# serializer.net
KiCad netlist of a schematic drawn in EAGLE
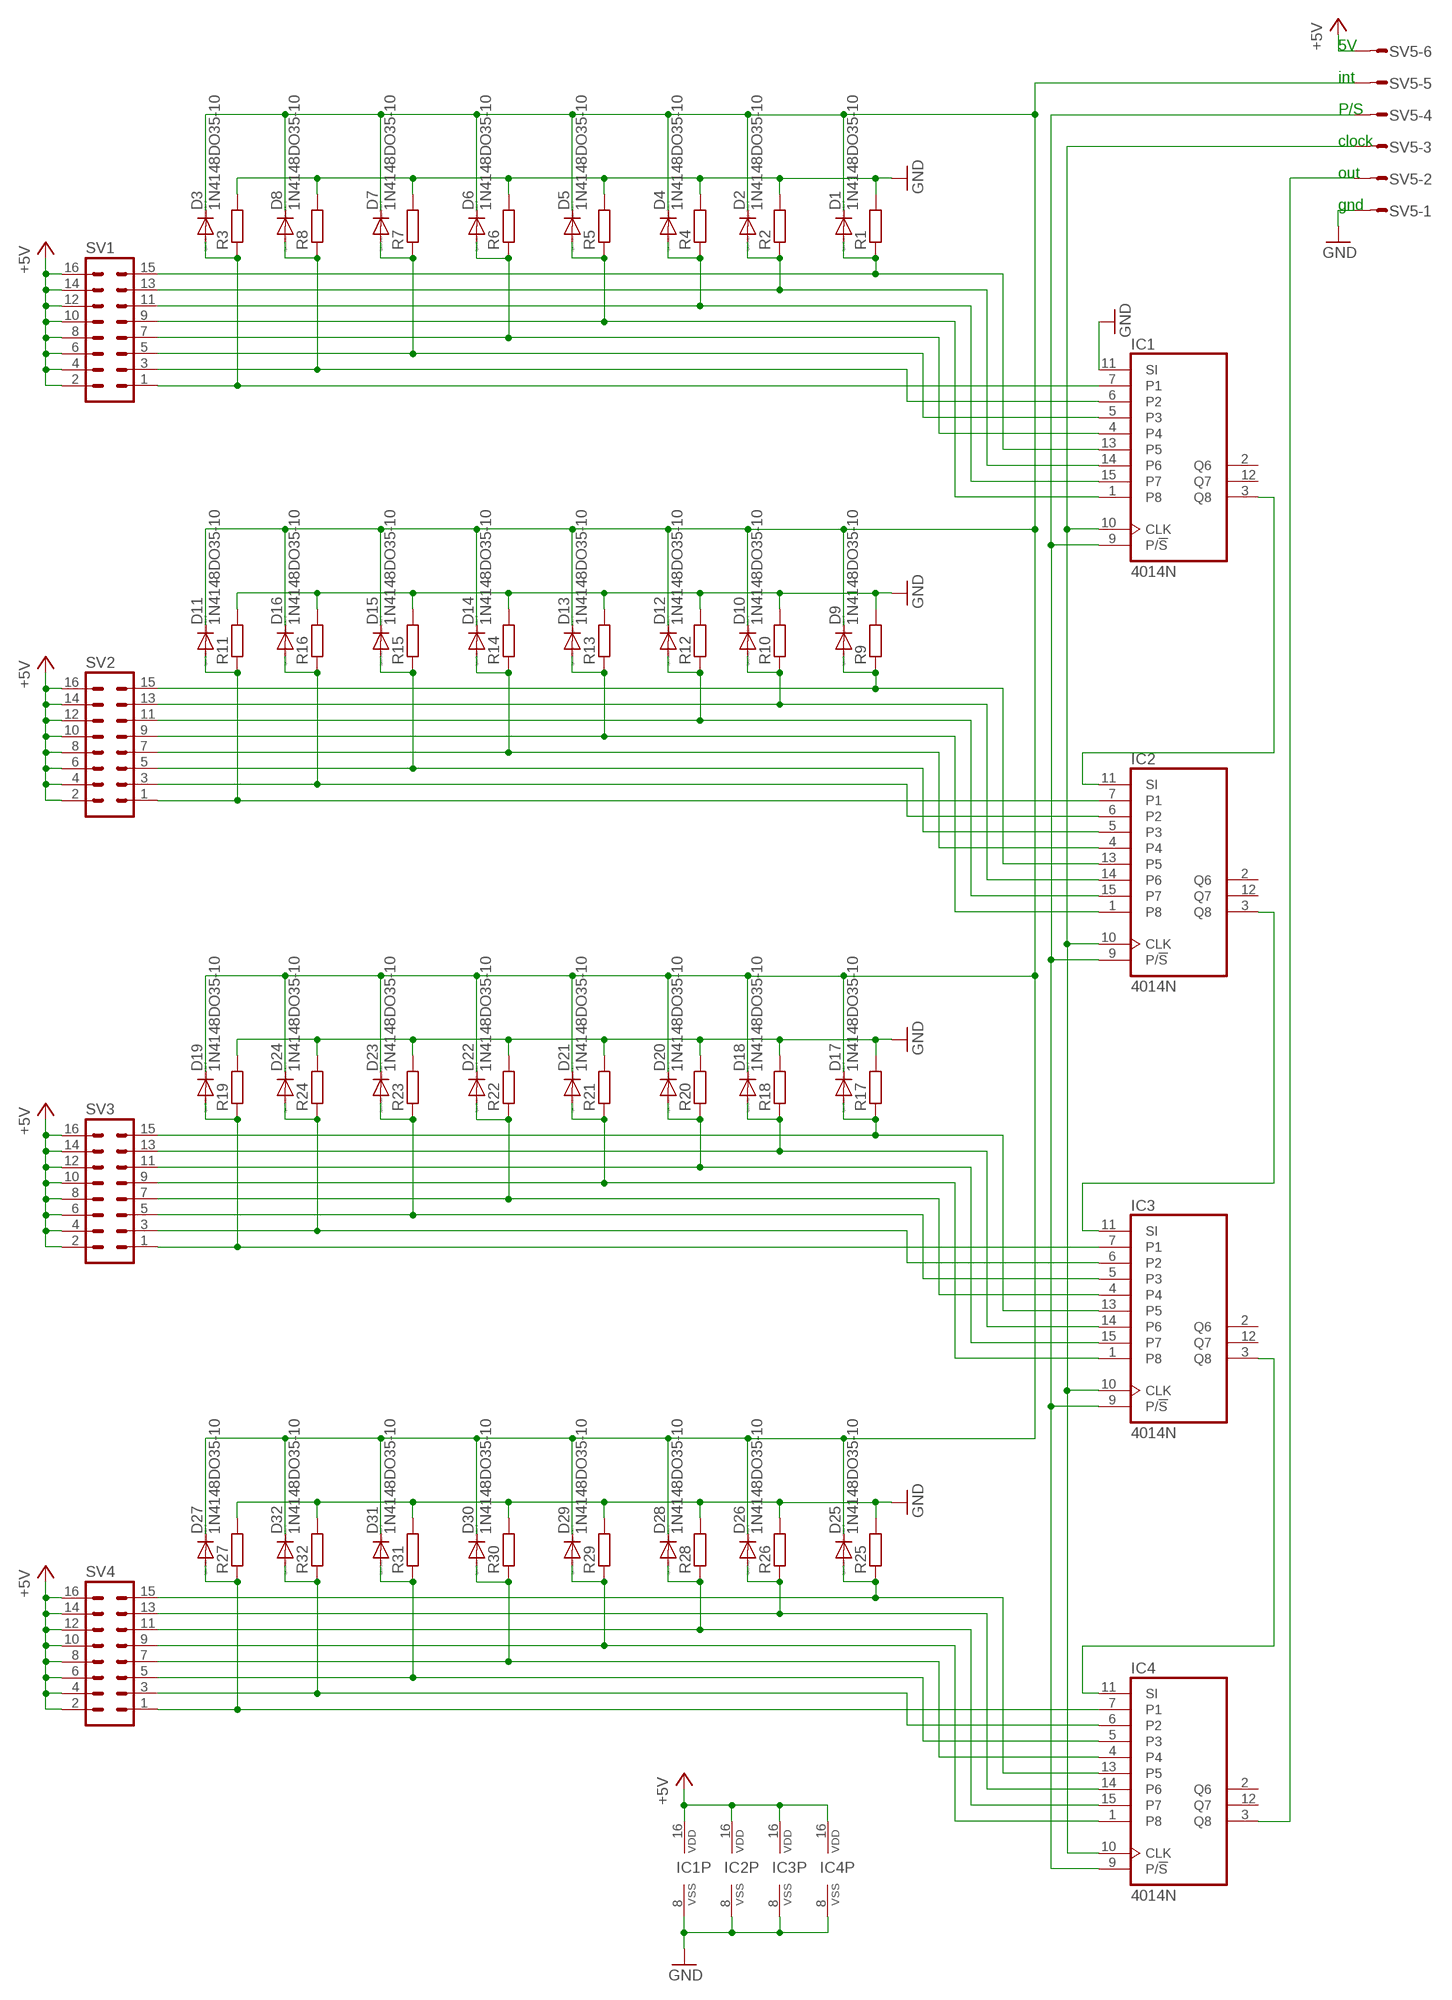
[diagram p0: schematic, sheet 1]

(export (version "E")
  (design (tool "Eeschema 10.0.6"))
  (components
    (comp (ref "D1")
      (value "1N4148DO35-10")
      (footprint "eagle-import:DO35-10")
      (libsource (lib "eagle-import") (part "1N4148DO35-10"))
    )
    (comp (ref "D2")
      (value "1N4148DO35-10")
      (footprint "eagle-import:DO35-10")
      (libsource (lib "eagle-import") (part "1N4148DO35-10"))
    )
    (comp (ref "D3")
      (value "1N4148DO35-10")
      (footprint "eagle-import:DO35-10")
      (libsource (lib "eagle-import") (part "1N4148DO35-10"))
    )
    (comp (ref "D4")
      (value "1N4148DO35-10")
      (footprint "eagle-import:DO35-10")
      (libsource (lib "eagle-import") (part "1N4148DO35-10"))
    )
    (comp (ref "D5")
      (value "1N4148DO35-10")
      (footprint "eagle-import:DO35-10")
      (libsource (lib "eagle-import") (part "1N4148DO35-10"))
    )
    (comp (ref "D6")
      (value "1N4148DO35-10")
      (footprint "eagle-import:DO35-10")
      (libsource (lib "eagle-import") (part "1N4148DO35-10"))
    )
    (comp (ref "D7")
      (value "1N4148DO35-10")
      (footprint "eagle-import:DO35-10")
      (libsource (lib "eagle-import") (part "1N4148DO35-10"))
    )
    (comp (ref "D8")
      (value "1N4148DO35-10")
      (footprint "eagle-import:DO35-10")
      (libsource (lib "eagle-import") (part "1N4148DO35-10"))
    )
    (comp (ref "D9")
      (value "1N4148DO35-10")
      (footprint "eagle-import:DO35-10")
      (libsource (lib "eagle-import") (part "1N4148DO35-10"))
    )
    (comp (ref "D10")
      (value "1N4148DO35-10")
      (footprint "eagle-import:DO35-10")
      (libsource (lib "eagle-import") (part "1N4148DO35-10"))
    )
    (comp (ref "D11")
      (value "1N4148DO35-10")
      (footprint "eagle-import:DO35-10")
      (libsource (lib "eagle-import") (part "1N4148DO35-10"))
    )
    (comp (ref "D12")
      (value "1N4148DO35-10")
      (footprint "eagle-import:DO35-10")
      (libsource (lib "eagle-import") (part "1N4148DO35-10"))
    )
    (comp (ref "D13")
      (value "1N4148DO35-10")
      (footprint "eagle-import:DO35-10")
      (libsource (lib "eagle-import") (part "1N4148DO35-10"))
    )
    (comp (ref "D14")
      (value "1N4148DO35-10")
      (footprint "eagle-import:DO35-10")
      (libsource (lib "eagle-import") (part "1N4148DO35-10"))
    )
    (comp (ref "D15")
      (value "1N4148DO35-10")
      (footprint "eagle-import:DO35-10")
      (libsource (lib "eagle-import") (part "1N4148DO35-10"))
    )
    (comp (ref "D16")
      (value "1N4148DO35-10")
      (footprint "eagle-import:DO35-10")
      (libsource (lib "eagle-import") (part "1N4148DO35-10"))
    )
    (comp (ref "D17")
      (value "1N4148DO35-10")
      (footprint "eagle-import:DO35-10")
      (libsource (lib "eagle-import") (part "1N4148DO35-10"))
    )
    (comp (ref "D18")
      (value "1N4148DO35-10")
      (footprint "eagle-import:DO35-10")
      (libsource (lib "eagle-import") (part "1N4148DO35-10"))
    )
    (comp (ref "D19")
      (value "1N4148DO35-10")
      (footprint "eagle-import:DO35-10")
      (libsource (lib "eagle-import") (part "1N4148DO35-10"))
    )
    (comp (ref "D20")
      (value "1N4148DO35-10")
      (footprint "eagle-import:DO35-10")
      (libsource (lib "eagle-import") (part "1N4148DO35-10"))
    )
    (comp (ref "D21")
      (value "1N4148DO35-10")
      (footprint "eagle-import:DO35-10")
      (libsource (lib "eagle-import") (part "1N4148DO35-10"))
    )
    (comp (ref "D22")
      (value "1N4148DO35-10")
      (footprint "eagle-import:DO35-10")
      (libsource (lib "eagle-import") (part "1N4148DO35-10"))
    )
    (comp (ref "D23")
      (value "1N4148DO35-10")
      (footprint "eagle-import:DO35-10")
      (libsource (lib "eagle-import") (part "1N4148DO35-10"))
    )
    (comp (ref "D24")
      (value "1N4148DO35-10")
      (footprint "eagle-import:DO35-10")
      (libsource (lib "eagle-import") (part "1N4148DO35-10"))
    )
    (comp (ref "D25")
      (value "1N4148DO35-10")
      (footprint "eagle-import:DO35-10")
      (libsource (lib "eagle-import") (part "1N4148DO35-10"))
    )
    (comp (ref "D26")
      (value "1N4148DO35-10")
      (footprint "eagle-import:DO35-10")
      (libsource (lib "eagle-import") (part "1N4148DO35-10"))
    )
    (comp (ref "D27")
      (value "1N4148DO35-10")
      (footprint "eagle-import:DO35-10")
      (libsource (lib "eagle-import") (part "1N4148DO35-10"))
    )
    (comp (ref "D28")
      (value "1N4148DO35-10")
      (footprint "eagle-import:DO35-10")
      (libsource (lib "eagle-import") (part "1N4148DO35-10"))
    )
    (comp (ref "D29")
      (value "1N4148DO35-10")
      (footprint "eagle-import:DO35-10")
      (libsource (lib "eagle-import") (part "1N4148DO35-10"))
    )
    (comp (ref "D30")
      (value "1N4148DO35-10")
      (footprint "eagle-import:DO35-10")
      (libsource (lib "eagle-import") (part "1N4148DO35-10"))
    )
    (comp (ref "D31")
      (value "1N4148DO35-10")
      (footprint "eagle-import:DO35-10")
      (libsource (lib "eagle-import") (part "1N4148DO35-10"))
    )
    (comp (ref "D32")
      (value "1N4148DO35-10")
      (footprint "eagle-import:DO35-10")
      (libsource (lib "eagle-import") (part "1N4148DO35-10"))
    )
    (comp (ref "IC1")
      (value "4014N")
      (footprint "eagle-import:DIL16")
      (libsource (lib "eagle-import") (part "4014N"))
    )
    (comp (ref "IC2")
      (value "4014N")
      (footprint "eagle-import:DIL16")
      (libsource (lib "eagle-import") (part "4014N"))
    )
    (comp (ref "IC3")
      (value "4014N")
      (footprint "eagle-import:DIL16")
      (libsource (lib "eagle-import") (part "4014N"))
    )
    (comp (ref "IC4")
      (value "4014N")
      (footprint "eagle-import:DIL16")
      (libsource (lib "eagle-import") (part "4014N"))
    )
    (comp (ref "R1")
      (value "R-EU_M1206")
      (footprint "eagle-import:M1206")
      (libsource (lib "eagle-import") (part "R-EU_M1206"))
    )
    (comp (ref "R2")
      (value "R-EU_M1206")
      (footprint "eagle-import:M1206")
      (libsource (lib "eagle-import") (part "R-EU_M1206"))
    )
    (comp (ref "R3")
      (value "R-EU_M1206")
      (footprint "eagle-import:M1206")
      (libsource (lib "eagle-import") (part "R-EU_M1206"))
    )
    (comp (ref "R4")
      (value "R-EU_M1206")
      (footprint "eagle-import:M1206")
      (libsource (lib "eagle-import") (part "R-EU_M1206"))
    )
    (comp (ref "R5")
      (value "R-EU_M1206")
      (footprint "eagle-import:M1206")
      (libsource (lib "eagle-import") (part "R-EU_M1206"))
    )
    (comp (ref "R6")
      (value "R-EU_M1206")
      (footprint "eagle-import:M1206")
      (libsource (lib "eagle-import") (part "R-EU_M1206"))
    )
    (comp (ref "R7")
      (value "R-EU_M1206")
      (footprint "eagle-import:M1206")
      (libsource (lib "eagle-import") (part "R-EU_M1206"))
    )
    (comp (ref "R8")
      (value "R-EU_M1206")
      (footprint "eagle-import:M1206")
      (libsource (lib "eagle-import") (part "R-EU_M1206"))
    )
    (comp (ref "R9")
      (value "R-EU_M1206")
      (footprint "eagle-import:M1206")
      (libsource (lib "eagle-import") (part "R-EU_M1206"))
    )
    (comp (ref "R10")
      (value "R-EU_M1206")
      (footprint "eagle-import:M1206")
      (libsource (lib "eagle-import") (part "R-EU_M1206"))
    )
    (comp (ref "R11")
      (value "R-EU_M1206")
      (footprint "eagle-import:M1206")
      (libsource (lib "eagle-import") (part "R-EU_M1206"))
    )
    (comp (ref "R12")
      (value "R-EU_M1206")
      (footprint "eagle-import:M1206")
      (libsource (lib "eagle-import") (part "R-EU_M1206"))
    )
    (comp (ref "R13")
      (value "R-EU_M1206")
      (footprint "eagle-import:M1206")
      (libsource (lib "eagle-import") (part "R-EU_M1206"))
    )
    (comp (ref "R14")
      (value "R-EU_M1206")
      (footprint "eagle-import:M1206")
      (libsource (lib "eagle-import") (part "R-EU_M1206"))
    )
    (comp (ref "R15")
      (value "R-EU_M1206")
      (footprint "eagle-import:M1206")
      (libsource (lib "eagle-import") (part "R-EU_M1206"))
    )
    (comp (ref "R16")
      (value "R-EU_M1206")
      (footprint "eagle-import:M1206")
      (libsource (lib "eagle-import") (part "R-EU_M1206"))
    )
    (comp (ref "R17")
      (value "R-EU_M1206")
      (footprint "eagle-import:M1206")
      (libsource (lib "eagle-import") (part "R-EU_M1206"))
    )
    (comp (ref "R18")
      (value "R-EU_M1206")
      (footprint "eagle-import:M1206")
      (libsource (lib "eagle-import") (part "R-EU_M1206"))
    )
    (comp (ref "R19")
      (value "R-EU_M1206")
      (footprint "eagle-import:M1206")
      (libsource (lib "eagle-import") (part "R-EU_M1206"))
    )
    (comp (ref "R20")
      (value "R-EU_M1206")
      (footprint "eagle-import:M1206")
      (libsource (lib "eagle-import") (part "R-EU_M1206"))
    )
    (comp (ref "R21")
      (value "R-EU_M1206")
      (footprint "eagle-import:M1206")
      (libsource (lib "eagle-import") (part "R-EU_M1206"))
    )
    (comp (ref "R22")
      (value "R-EU_M1206")
      (footprint "eagle-import:M1206")
      (libsource (lib "eagle-import") (part "R-EU_M1206"))
    )
    (comp (ref "R23")
      (value "R-EU_M1206")
      (footprint "eagle-import:M1206")
      (libsource (lib "eagle-import") (part "R-EU_M1206"))
    )
    (comp (ref "R24")
      (value "R-EU_M1206")
      (footprint "eagle-import:M1206")
      (libsource (lib "eagle-import") (part "R-EU_M1206"))
    )
    (comp (ref "R25")
      (value "R-EU_M1206")
      (footprint "eagle-import:M1206")
      (libsource (lib "eagle-import") (part "R-EU_M1206"))
    )
    (comp (ref "R26")
      (value "R-EU_M1206")
      (footprint "eagle-import:M1206")
      (libsource (lib "eagle-import") (part "R-EU_M1206"))
    )
    (comp (ref "R27")
      (value "R-EU_M1206")
      (footprint "eagle-import:M1206")
      (libsource (lib "eagle-import") (part "R-EU_M1206"))
    )
    (comp (ref "R28")
      (value "R-EU_M1206")
      (footprint "eagle-import:M1206")
      (libsource (lib "eagle-import") (part "R-EU_M1206"))
    )
    (comp (ref "R29")
      (value "R-EU_M1206")
      (footprint "eagle-import:M1206")
      (libsource (lib "eagle-import") (part "R-EU_M1206"))
    )
    (comp (ref "R30")
      (value "R-EU_M1206")
      (footprint "eagle-import:M1206")
      (libsource (lib "eagle-import") (part "R-EU_M1206"))
    )
    (comp (ref "R31")
      (value "R-EU_M1206")
      (footprint "eagle-import:M1206")
      (libsource (lib "eagle-import") (part "R-EU_M1206"))
    )
    (comp (ref "R32")
      (value "R-EU_M1206")
      (footprint "eagle-import:M1206")
      (libsource (lib "eagle-import") (part "R-EU_M1206"))
    )
    (comp (ref "SV1")
      (value "MA08-2")
      (footprint "eagle-import:MA08-2")
      (libsource (lib "eagle-import") (part "MA08-2"))
    )
    (comp (ref "SV2")
      (value "MA08-2")
      (footprint "eagle-import:MA08-2")
      (libsource (lib "eagle-import") (part "MA08-2"))
    )
    (comp (ref "SV3")
      (value "MA08-2")
      (footprint "eagle-import:MA08-2")
      (libsource (lib "eagle-import") (part "MA08-2"))
    )
    (comp (ref "SV4")
      (value "MA08-2")
      (footprint "eagle-import:MA08-2")
      (libsource (lib "eagle-import") (part "MA08-2"))
    )
    (comp (ref "SV5")
      (value "S06P")
      (footprint "eagle-import:S06P")
      (libsource (lib "eagle-import") (part "S06P"))
    )
  )
  (nets
    (net (code "1") (name "+5V") (class "Default")
      (node (ref "IC1") (pin "16") (pinfunction "VDD_16") (pintype "power_in"))
      (node (ref "IC2") (pin "16") (pinfunction "VDD_16") (pintype "power_in"))
      (node (ref "IC3") (pin "16") (pinfunction "VDD_16") (pintype "power_in"))
      (node (ref "IC4") (pin "16") (pinfunction "VDD_16") (pintype "power_in"))
      (node (ref "SV1") (pin "10") (pinfunction "10_10") (pintype "passive"))
      (node (ref "SV1") (pin "12") (pinfunction "12_12") (pintype "passive"))
      (node (ref "SV1") (pin "14") (pinfunction "14_14") (pintype "passive"))
      (node (ref "SV1") (pin "16") (pinfunction "16_16") (pintype "passive"))
      (node (ref "SV1") (pin "2") (pinfunction "2_2") (pintype "passive"))
      (node (ref "SV1") (pin "4") (pinfunction "4_4") (pintype "passive"))
      (node (ref "SV1") (pin "6") (pinfunction "6_6") (pintype "passive"))
      (node (ref "SV1") (pin "8") (pinfunction "8_8") (pintype "passive"))
      (node (ref "SV2") (pin "10") (pinfunction "10_10") (pintype "passive"))
      (node (ref "SV2") (pin "12") (pinfunction "12_12") (pintype "passive"))
      (node (ref "SV2") (pin "14") (pinfunction "14_14") (pintype "passive"))
      (node (ref "SV2") (pin "16") (pinfunction "16_16") (pintype "passive"))
      (node (ref "SV2") (pin "2") (pinfunction "2_2") (pintype "passive"))
      (node (ref "SV2") (pin "4") (pinfunction "4_4") (pintype "passive"))
      (node (ref "SV2") (pin "6") (pinfunction "6_6") (pintype "passive"))
      (node (ref "SV2") (pin "8") (pinfunction "8_8") (pintype "passive"))
      (node (ref "SV3") (pin "10") (pinfunction "10_10") (pintype "passive"))
      (node (ref "SV3") (pin "12") (pinfunction "12_12") (pintype "passive"))
      (node (ref "SV3") (pin "14") (pinfunction "14_14") (pintype "passive"))
      (node (ref "SV3") (pin "16") (pinfunction "16_16") (pintype "passive"))
      (node (ref "SV3") (pin "2") (pinfunction "2_2") (pintype "passive"))
      (node (ref "SV3") (pin "4") (pinfunction "4_4") (pintype "passive"))
      (node (ref "SV3") (pin "6") (pinfunction "6_6") (pintype "passive"))
      (node (ref "SV3") (pin "8") (pinfunction "8_8") (pintype "passive"))
      (node (ref "SV4") (pin "10") (pinfunction "10_10") (pintype "passive"))
      (node (ref "SV4") (pin "12") (pinfunction "12_12") (pintype "passive"))
      (node (ref "SV4") (pin "14") (pinfunction "14_14") (pintype "passive"))
      (node (ref "SV4") (pin "16") (pinfunction "16_16") (pintype "passive"))
      (node (ref "SV4") (pin "2") (pinfunction "2_2") (pintype "passive"))
      (node (ref "SV4") (pin "4") (pinfunction "4_4") (pintype "passive"))
      (node (ref "SV4") (pin "6") (pinfunction "6_6") (pintype "passive"))
      (node (ref "SV4") (pin "8") (pinfunction "8_8") (pintype "passive"))
      (node (ref "SV5") (pin "6") (pinfunction "S_6") (pintype "passive"))
    )
    (net (code "2") (name "GND") (class "Default")
      (node (ref "IC1") (pin "11") (pinfunction "SI_11") (pintype "input"))
      (node (ref "IC1") (pin "8") (pinfunction "VSS_8") (pintype "power_in"))
      (node (ref "IC2") (pin "8") (pinfunction "VSS_8") (pintype "power_in"))
      (node (ref "IC3") (pin "8") (pinfunction "VSS_8") (pintype "power_in"))
      (node (ref "IC4") (pin "8") (pinfunction "VSS_8") (pintype "power_in"))
      (node (ref "R1") (pin "2") (pinfunction "2_2") (pintype "passive"))
      (node (ref "R10") (pin "2") (pinfunction "2_2") (pintype "passive"))
      (node (ref "R11") (pin "2") (pinfunction "2_2") (pintype "passive"))
      (node (ref "R12") (pin "2") (pinfunction "2_2") (pintype "passive"))
      (node (ref "R13") (pin "2") (pinfunction "2_2") (pintype "passive"))
      (node (ref "R14") (pin "2") (pinfunction "2_2") (pintype "passive"))
      (node (ref "R15") (pin "2") (pinfunction "2_2") (pintype "passive"))
      (node (ref "R16") (pin "2") (pinfunction "2_2") (pintype "passive"))
      (node (ref "R17") (pin "2") (pinfunction "2_2") (pintype "passive"))
      (node (ref "R18") (pin "2") (pinfunction "2_2") (pintype "passive"))
      (node (ref "R19") (pin "2") (pinfunction "2_2") (pintype "passive"))
      (node (ref "R2") (pin "2") (pinfunction "2_2") (pintype "passive"))
      (node (ref "R20") (pin "2") (pinfunction "2_2") (pintype "passive"))
      (node (ref "R21") (pin "2") (pinfunction "2_2") (pintype "passive"))
      (node (ref "R22") (pin "2") (pinfunction "2_2") (pintype "passive"))
      (node (ref "R23") (pin "2") (pinfunction "2_2") (pintype "passive"))
      (node (ref "R24") (pin "2") (pinfunction "2_2") (pintype "passive"))
      (node (ref "R25") (pin "2") (pinfunction "2_2") (pintype "passive"))
      (node (ref "R26") (pin "2") (pinfunction "2_2") (pintype "passive"))
      (node (ref "R27") (pin "2") (pinfunction "2_2") (pintype "passive"))
      (node (ref "R28") (pin "2") (pinfunction "2_2") (pintype "passive"))
      (node (ref "R29") (pin "2") (pinfunction "2_2") (pintype "passive"))
      (node (ref "R3") (pin "2") (pinfunction "2_2") (pintype "passive"))
      (node (ref "R30") (pin "2") (pinfunction "2_2") (pintype "passive"))
      (node (ref "R31") (pin "2") (pinfunction "2_2") (pintype "passive"))
      (node (ref "R32") (pin "2") (pinfunction "2_2") (pintype "passive"))
      (node (ref "R4") (pin "2") (pinfunction "2_2") (pintype "passive"))
      (node (ref "R5") (pin "2") (pinfunction "2_2") (pintype "passive"))
      (node (ref "R6") (pin "2") (pinfunction "2_2") (pintype "passive"))
      (node (ref "R7") (pin "2") (pinfunction "2_2") (pintype "passive"))
      (node (ref "R8") (pin "2") (pinfunction "2_2") (pintype "passive"))
      (node (ref "R9") (pin "2") (pinfunction "2_2") (pintype "passive"))
      (node (ref "SV5") (pin "1") (pinfunction "S_1") (pintype "passive"))
    )
    (net (code "3") (name "Net-(IC1A-CLK)") (class "Default")
      (node (ref "IC1") (pin "10") (pinfunction "CLK_10") (pintype "input"))
      (node (ref "IC2") (pin "10") (pinfunction "CLK_10") (pintype "input"))
      (node (ref "IC3") (pin "10") (pinfunction "CLK_10") (pintype "input"))
      (node (ref "IC4") (pin "10") (pinfunction "CLK_10") (pintype "input"))
      (node (ref "SV5") (pin "3") (pinfunction "S_3") (pintype "passive"))
    )
    (net (code "4") (name "Net-(IC1A-P1)") (class "Default")
      (node (ref "D3") (pin "A") (pinfunction "A_A") (pintype "passive"))
      (node (ref "IC1") (pin "7") (pinfunction "P1_7") (pintype "input"))
      (node (ref "R3") (pin "1") (pinfunction "1_1") (pintype "passive"))
      (node (ref "SV1") (pin "1") (pinfunction "1_1") (pintype "passive"))
    )
    (net (code "5") (name "Net-(IC1A-P2)") (class "Default")
      (node (ref "D8") (pin "A") (pinfunction "A_A") (pintype "passive"))
      (node (ref "IC1") (pin "6") (pinfunction "P2_6") (pintype "input"))
      (node (ref "R8") (pin "1") (pinfunction "1_1") (pintype "passive"))
      (node (ref "SV1") (pin "3") (pinfunction "3_3") (pintype "passive"))
    )
    (net (code "6") (name "Net-(IC1A-P3)") (class "Default")
      (node (ref "D7") (pin "A") (pinfunction "A_A") (pintype "passive"))
      (node (ref "IC1") (pin "5") (pinfunction "P3_5") (pintype "input"))
      (node (ref "R7") (pin "1") (pinfunction "1_1") (pintype "passive"))
      (node (ref "SV1") (pin "5") (pinfunction "5_5") (pintype "passive"))
    )
    (net (code "7") (name "Net-(IC1A-P4)") (class "Default")
      (node (ref "D6") (pin "A") (pinfunction "A_A") (pintype "passive"))
      (node (ref "IC1") (pin "4") (pinfunction "P4_4") (pintype "input"))
      (node (ref "R6") (pin "1") (pinfunction "1_1") (pintype "passive"))
      (node (ref "SV1") (pin "7") (pinfunction "7_7") (pintype "passive"))
    )
    (net (code "8") (name "Net-(IC1A-P5)") (class "Default")
      (node (ref "D1") (pin "A") (pinfunction "A_A") (pintype "passive"))
      (node (ref "IC1") (pin "13") (pinfunction "P5_13") (pintype "input"))
      (node (ref "R1") (pin "1") (pinfunction "1_1") (pintype "passive"))
      (node (ref "SV1") (pin "15") (pinfunction "15_15") (pintype "passive"))
    )
    (net (code "9") (name "Net-(IC1A-P6)") (class "Default")
      (node (ref "D2") (pin "A") (pinfunction "A_A") (pintype "passive"))
      (node (ref "IC1") (pin "14") (pinfunction "P6_14") (pintype "input"))
      (node (ref "R2") (pin "1") (pinfunction "1_1") (pintype "passive"))
      (node (ref "SV1") (pin "13") (pinfunction "13_13") (pintype "passive"))
    )
    (net (code "10") (name "Net-(IC1A-P7)") (class "Default")
      (node (ref "D4") (pin "A") (pinfunction "A_A") (pintype "passive"))
      (node (ref "IC1") (pin "15") (pinfunction "P7_15") (pintype "input"))
      (node (ref "R4") (pin "1") (pinfunction "1_1") (pintype "passive"))
      (node (ref "SV1") (pin "11") (pinfunction "11_11") (pintype "passive"))
    )
    (net (code "11") (name "Net-(IC1A-P8)") (class "Default")
      (node (ref "D5") (pin "A") (pinfunction "A_A") (pintype "passive"))
      (node (ref "IC1") (pin "1") (pinfunction "P8_1") (pintype "input"))
      (node (ref "R5") (pin "1") (pinfunction "1_1") (pintype "passive"))
      (node (ref "SV1") (pin "9") (pinfunction "9_9") (pintype "passive"))
    )
    (net (code "12") (name "Net-(IC1A-P{slash}~{S})") (class "Default")
      (node (ref "IC1") (pin "9") (pinfunction "P/~{S}_9") (pintype "input"))
      (node (ref "IC2") (pin "9") (pinfunction "P/~{S}_9") (pintype "input"))
      (node (ref "IC3") (pin "9") (pinfunction "P/~{S}_9") (pintype "input"))
      (node (ref "IC4") (pin "9") (pinfunction "P/~{S}_9") (pintype "input"))
      (node (ref "SV5") (pin "4") (pinfunction "S_4") (pintype "passive"))
    )
    (net (code "13") (name "Net-(IC1A-Q8)") (class "Default")
      (node (ref "IC1") (pin "3") (pinfunction "Q8_3") (pintype "output"))
      (node (ref "IC2") (pin "11") (pinfunction "SI_11") (pintype "input"))
    )
    (net (code "14") (name "Net-(IC2A-P1)") (class "Default")
      (node (ref "D11") (pin "A") (pinfunction "A_A") (pintype "passive"))
      (node (ref "IC2") (pin "7") (pinfunction "P1_7") (pintype "input"))
      (node (ref "R11") (pin "1") (pinfunction "1_1") (pintype "passive"))
      (node (ref "SV2") (pin "1") (pinfunction "1_1") (pintype "passive"))
    )
    (net (code "15") (name "Net-(IC2A-P2)") (class "Default")
      (node (ref "D16") (pin "A") (pinfunction "A_A") (pintype "passive"))
      (node (ref "IC2") (pin "6") (pinfunction "P2_6") (pintype "input"))
      (node (ref "R16") (pin "1") (pinfunction "1_1") (pintype "passive"))
      (node (ref "SV2") (pin "3") (pinfunction "3_3") (pintype "passive"))
    )
    (net (code "16") (name "Net-(IC2A-P3)") (class "Default")
      (node (ref "D15") (pin "A") (pinfunction "A_A") (pintype "passive"))
      (node (ref "IC2") (pin "5") (pinfunction "P3_5") (pintype "input"))
      (node (ref "R15") (pin "1") (pinfunction "1_1") (pintype "passive"))
      (node (ref "SV2") (pin "5") (pinfunction "5_5") (pintype "passive"))
    )
    (net (code "17") (name "Net-(IC2A-P4)") (class "Default")
      (node (ref "D14") (pin "A") (pinfunction "A_A") (pintype "passive"))
      (node (ref "IC2") (pin "4") (pinfunction "P4_4") (pintype "input"))
      (node (ref "R14") (pin "1") (pinfunction "1_1") (pintype "passive"))
      (node (ref "SV2") (pin "7") (pinfunction "7_7") (pintype "passive"))
    )
    (net (code "18") (name "Net-(IC2A-P5)") (class "Default")
      (node (ref "D9") (pin "A") (pinfunction "A_A") (pintype "passive"))
      (node (ref "IC2") (pin "13") (pinfunction "P5_13") (pintype "input"))
      (node (ref "R9") (pin "1") (pinfunction "1_1") (pintype "passive"))
      (node (ref "SV2") (pin "15") (pinfunction "15_15") (pintype "passive"))
    )
    (net (code "19") (name "Net-(IC2A-P6)") (class "Default")
      (node (ref "D10") (pin "A") (pinfunction "A_A") (pintype "passive"))
      (node (ref "IC2") (pin "14") (pinfunction "P6_14") (pintype "input"))
      (node (ref "R10") (pin "1") (pinfunction "1_1") (pintype "passive"))
      (node (ref "SV2") (pin "13") (pinfunction "13_13") (pintype "passive"))
    )
    (net (code "20") (name "Net-(IC2A-P7)") (class "Default")
      (node (ref "D12") (pin "A") (pinfunction "A_A") (pintype "passive"))
      (node (ref "IC2") (pin "15") (pinfunction "P7_15") (pintype "input"))
      (node (ref "R12") (pin "1") (pinfunction "1_1") (pintype "passive"))
      (node (ref "SV2") (pin "11") (pinfunction "11_11") (pintype "passive"))
    )
    (net (code "21") (name "Net-(IC2A-P8)") (class "Default")
      (node (ref "D13") (pin "A") (pinfunction "A_A") (pintype "passive"))
      (node (ref "IC2") (pin "1") (pinfunction "P8_1") (pintype "input"))
      (node (ref "R13") (pin "1") (pinfunction "1_1") (pintype "passive"))
      (node (ref "SV2") (pin "9") (pinfunction "9_9") (pintype "passive"))
    )
    (net (code "22") (name "Net-(IC2A-Q8)") (class "Default")
      (node (ref "IC2") (pin "3") (pinfunction "Q8_3") (pintype "output"))
      (node (ref "IC3") (pin "11") (pinfunction "SI_11") (pintype "input"))
    )
    (net (code "23") (name "Net-(IC3A-P1)") (class "Default")
      (node (ref "D19") (pin "A") (pinfunction "A_A") (pintype "passive"))
      (node (ref "IC3") (pin "7") (pinfunction "P1_7") (pintype "input"))
      (node (ref "R19") (pin "1") (pinfunction "1_1") (pintype "passive"))
      (node (ref "SV3") (pin "1") (pinfunction "1_1") (pintype "passive"))
    )
    (net (code "24") (name "Net-(IC3A-P2)") (class "Default")
      (node (ref "D24") (pin "A") (pinfunction "A_A") (pintype "passive"))
      (node (ref "IC3") (pin "6") (pinfunction "P2_6") (pintype "input"))
      (node (ref "R24") (pin "1") (pinfunction "1_1") (pintype "passive"))
      (node (ref "SV3") (pin "3") (pinfunction "3_3") (pintype "passive"))
    )
    (net (code "25") (name "Net-(IC3A-P3)") (class "Default")
      (node (ref "D23") (pin "A") (pinfunction "A_A") (pintype "passive"))
      (node (ref "IC3") (pin "5") (pinfunction "P3_5") (pintype "input"))
      (node (ref "R23") (pin "1") (pinfunction "1_1") (pintype "passive"))
      (node (ref "SV3") (pin "5") (pinfunction "5_5") (pintype "passive"))
    )
    (net (code "26") (name "Net-(IC3A-P4)") (class "Default")
      (node (ref "D22") (pin "A") (pinfunction "A_A") (pintype "passive"))
      (node (ref "IC3") (pin "4") (pinfunction "P4_4") (pintype "input"))
      (node (ref "R22") (pin "1") (pinfunction "1_1") (pintype "passive"))
      (node (ref "SV3") (pin "7") (pinfunction "7_7") (pintype "passive"))
    )
    (net (code "27") (name "Net-(IC3A-P5)") (class "Default")
      (node (ref "D17") (pin "A") (pinfunction "A_A") (pintype "passive"))
      (node (ref "IC3") (pin "13") (pinfunction "P5_13") (pintype "input"))
      (node (ref "R17") (pin "1") (pinfunction "1_1") (pintype "passive"))
      (node (ref "SV3") (pin "15") (pinfunction "15_15") (pintype "passive"))
    )
    (net (code "28") (name "Net-(IC3A-P6)") (class "Default")
      (node (ref "D18") (pin "A") (pinfunction "A_A") (pintype "passive"))
      (node (ref "IC3") (pin "14") (pinfunction "P6_14") (pintype "input"))
      (node (ref "R18") (pin "1") (pinfunction "1_1") (pintype "passive"))
      (node (ref "SV3") (pin "13") (pinfunction "13_13") (pintype "passive"))
    )
    (net (code "29") (name "Net-(IC3A-P7)") (class "Default")
      (node (ref "D20") (pin "A") (pinfunction "A_A") (pintype "passive"))
      (node (ref "IC3") (pin "15") (pinfunction "P7_15") (pintype "input"))
      (node (ref "R20") (pin "1") (pinfunction "1_1") (pintype "passive"))
      (node (ref "SV3") (pin "11") (pinfunction "11_11") (pintype "passive"))
    )
    (net (code "30") (name "Net-(IC3A-P8)") (class "Default")
      (node (ref "D21") (pin "A") (pinfunction "A_A") (pintype "passive"))
      (node (ref "IC3") (pin "1") (pinfunction "P8_1") (pintype "input"))
      (node (ref "R21") (pin "1") (pinfunction "1_1") (pintype "passive"))
      (node (ref "SV3") (pin "9") (pinfunction "9_9") (pintype "passive"))
    )
    (net (code "31") (name "Net-(IC3A-Q8)") (class "Default")
      (node (ref "IC3") (pin "3") (pinfunction "Q8_3") (pintype "output"))
      (node (ref "IC4") (pin "11") (pinfunction "SI_11") (pintype "input"))
    )
    (net (code "32") (name "Net-(IC4A-P1)") (class "Default")
      (node (ref "D27") (pin "A") (pinfunction "A_A") (pintype "passive"))
      (node (ref "IC4") (pin "7") (pinfunction "P1_7") (pintype "input"))
      (node (ref "R27") (pin "1") (pinfunction "1_1") (pintype "passive"))
      (node (ref "SV4") (pin "1") (pinfunction "1_1") (pintype "passive"))
    )
    (net (code "33") (name "Net-(IC4A-P2)") (class "Default")
      (node (ref "D32") (pin "A") (pinfunction "A_A") (pintype "passive"))
      (node (ref "IC4") (pin "6") (pinfunction "P2_6") (pintype "input"))
      (node (ref "R32") (pin "1") (pinfunction "1_1") (pintype "passive"))
      (node (ref "SV4") (pin "3") (pinfunction "3_3") (pintype "passive"))
    )
    (net (code "34") (name "Net-(IC4A-P3)") (class "Default")
      (node (ref "D31") (pin "A") (pinfunction "A_A") (pintype "passive"))
      (node (ref "IC4") (pin "5") (pinfunction "P3_5") (pintype "input"))
      (node (ref "R31") (pin "1") (pinfunction "1_1") (pintype "passive"))
      (node (ref "SV4") (pin "5") (pinfunction "5_5") (pintype "passive"))
    )
    (net (code "35") (name "Net-(IC4A-P4)") (class "Default")
      (node (ref "D30") (pin "A") (pinfunction "A_A") (pintype "passive"))
      (node (ref "IC4") (pin "4") (pinfunction "P4_4") (pintype "input"))
      (node (ref "R30") (pin "1") (pinfunction "1_1") (pintype "passive"))
      (node (ref "SV4") (pin "7") (pinfunction "7_7") (pintype "passive"))
    )
    (net (code "36") (name "Net-(IC4A-P5)") (class "Default")
      (node (ref "D25") (pin "A") (pinfunction "A_A") (pintype "passive"))
      (node (ref "IC4") (pin "13") (pinfunction "P5_13") (pintype "input"))
      (node (ref "R25") (pin "1") (pinfunction "1_1") (pintype "passive"))
      (node (ref "SV4") (pin "15") (pinfunction "15_15") (pintype "passive"))
    )
    (net (code "37") (name "Net-(IC4A-P6)") (class "Default")
      (node (ref "D26") (pin "A") (pinfunction "A_A") (pintype "passive"))
      (node (ref "IC4") (pin "14") (pinfunction "P6_14") (pintype "input"))
      (node (ref "R26") (pin "1") (pinfunction "1_1") (pintype "passive"))
      (node (ref "SV4") (pin "13") (pinfunction "13_13") (pintype "passive"))
    )
    (net (code "38") (name "Net-(IC4A-P7)") (class "Default")
      (node (ref "D28") (pin "A") (pinfunction "A_A") (pintype "passive"))
      (node (ref "IC4") (pin "15") (pinfunction "P7_15") (pintype "input"))
      (node (ref "R28") (pin "1") (pinfunction "1_1") (pintype "passive"))
      (node (ref "SV4") (pin "11") (pinfunction "11_11") (pintype "passive"))
    )
    (net (code "39") (name "Net-(IC4A-P8)") (class "Default")
      (node (ref "D29") (pin "A") (pinfunction "A_A") (pintype "passive"))
      (node (ref "IC4") (pin "1") (pinfunction "P8_1") (pintype "input"))
      (node (ref "R29") (pin "1") (pinfunction "1_1") (pintype "passive"))
      (node (ref "SV4") (pin "9") (pinfunction "9_9") (pintype "passive"))
    )
    (net (code "40") (name "Net-(IC4A-Q8)") (class "Default")
      (node (ref "IC4") (pin "3") (pinfunction "Q8_3") (pintype "output"))
      (node (ref "SV5") (pin "2") (pinfunction "S_2") (pintype "passive"))
    )
    (net (code "41") (name "Net-(SV5E-S)") (class "Default")
      (node (ref "D1") (pin "C") (pinfunction "C_C") (pintype "passive"))
      (node (ref "D10") (pin "C") (pinfunction "C_C") (pintype "passive"))
      (node (ref "D11") (pin "C") (pinfunction "C_C") (pintype "passive"))
      (node (ref "D12") (pin "C") (pinfunction "C_C") (pintype "passive"))
      (node (ref "D13") (pin "C") (pinfunction "C_C") (pintype "passive"))
      (node (ref "D14") (pin "C") (pinfunction "C_C") (pintype "passive"))
      (node (ref "D15") (pin "C") (pinfunction "C_C") (pintype "passive"))
      (node (ref "D16") (pin "C") (pinfunction "C_C") (pintype "passive"))
      (node (ref "D17") (pin "C") (pinfunction "C_C") (pintype "passive"))
      (node (ref "D18") (pin "C") (pinfunction "C_C") (pintype "passive"))
      (node (ref "D19") (pin "C") (pinfunction "C_C") (pintype "passive"))
      (node (ref "D2") (pin "C") (pinfunction "C_C") (pintype "passive"))
      (node (ref "D20") (pin "C") (pinfunction "C_C") (pintype "passive"))
      (node (ref "D21") (pin "C") (pinfunction "C_C") (pintype "passive"))
      (node (ref "D22") (pin "C") (pinfunction "C_C") (pintype "passive"))
      (node (ref "D23") (pin "C") (pinfunction "C_C") (pintype "passive"))
      (node (ref "D24") (pin "C") (pinfunction "C_C") (pintype "passive"))
      (node (ref "D25") (pin "C") (pinfunction "C_C") (pintype "passive"))
      (node (ref "D26") (pin "C") (pinfunction "C_C") (pintype "passive"))
      (node (ref "D27") (pin "C") (pinfunction "C_C") (pintype "passive"))
      (node (ref "D28") (pin "C") (pinfunction "C_C") (pintype "passive"))
      (node (ref "D29") (pin "C") (pinfunction "C_C") (pintype "passive"))
      (node (ref "D3") (pin "C") (pinfunction "C_C") (pintype "passive"))
      (node (ref "D30") (pin "C") (pinfunction "C_C") (pintype "passive"))
      (node (ref "D31") (pin "C") (pinfunction "C_C") (pintype "passive"))
      (node (ref "D32") (pin "C") (pinfunction "C_C") (pintype "passive"))
      (node (ref "D4") (pin "C") (pinfunction "C_C") (pintype "passive"))
      (node (ref "D5") (pin "C") (pinfunction "C_C") (pintype "passive"))
      (node (ref "D6") (pin "C") (pinfunction "C_C") (pintype "passive"))
      (node (ref "D7") (pin "C") (pinfunction "C_C") (pintype "passive"))
      (node (ref "D8") (pin "C") (pinfunction "C_C") (pintype "passive"))
      (node (ref "D9") (pin "C") (pinfunction "C_C") (pintype "passive"))
      (node (ref "SV5") (pin "5") (pinfunction "S_5") (pintype "passive"))
    )
    (net (code "42") (name "unconnected-(IC1A-Q6-Pad2)") (class "Default")
      (node (ref "IC1") (pin "2") (pinfunction "Q6_2") (pintype "output"))
    )
    (net (code "43") (name "unconnected-(IC1A-Q7-Pad12)") (class "Default")
      (node (ref "IC1") (pin "12") (pinfunction "Q7_12") (pintype "output"))
    )
    (net (code "44") (name "unconnected-(IC2A-Q6-Pad2)") (class "Default")
      (node (ref "IC2") (pin "2") (pinfunction "Q6_2") (pintype "output"))
    )
    (net (code "45") (name "unconnected-(IC2A-Q7-Pad12)") (class "Default")
      (node (ref "IC2") (pin "12") (pinfunction "Q7_12") (pintype "output"))
    )
    (net (code "46") (name "unconnected-(IC3A-Q6-Pad2)") (class "Default")
      (node (ref "IC3") (pin "2") (pinfunction "Q6_2") (pintype "output"))
    )
    (net (code "47") (name "unconnected-(IC3A-Q7-Pad12)") (class "Default")
      (node (ref "IC3") (pin "12") (pinfunction "Q7_12") (pintype "output"))
    )
    (net (code "48") (name "unconnected-(IC4A-Q6-Pad2)") (class "Default")
      (node (ref "IC4") (pin "2") (pinfunction "Q6_2") (pintype "output"))
    )
    (net (code "49") (name "unconnected-(IC4A-Q7-Pad12)") (class "Default")
      (node (ref "IC4") (pin "12") (pinfunction "Q7_12") (pintype "output"))
    )
  )
)
